# Sheet2.net
KiCad netlist of a schematic drawn in Altium Designer
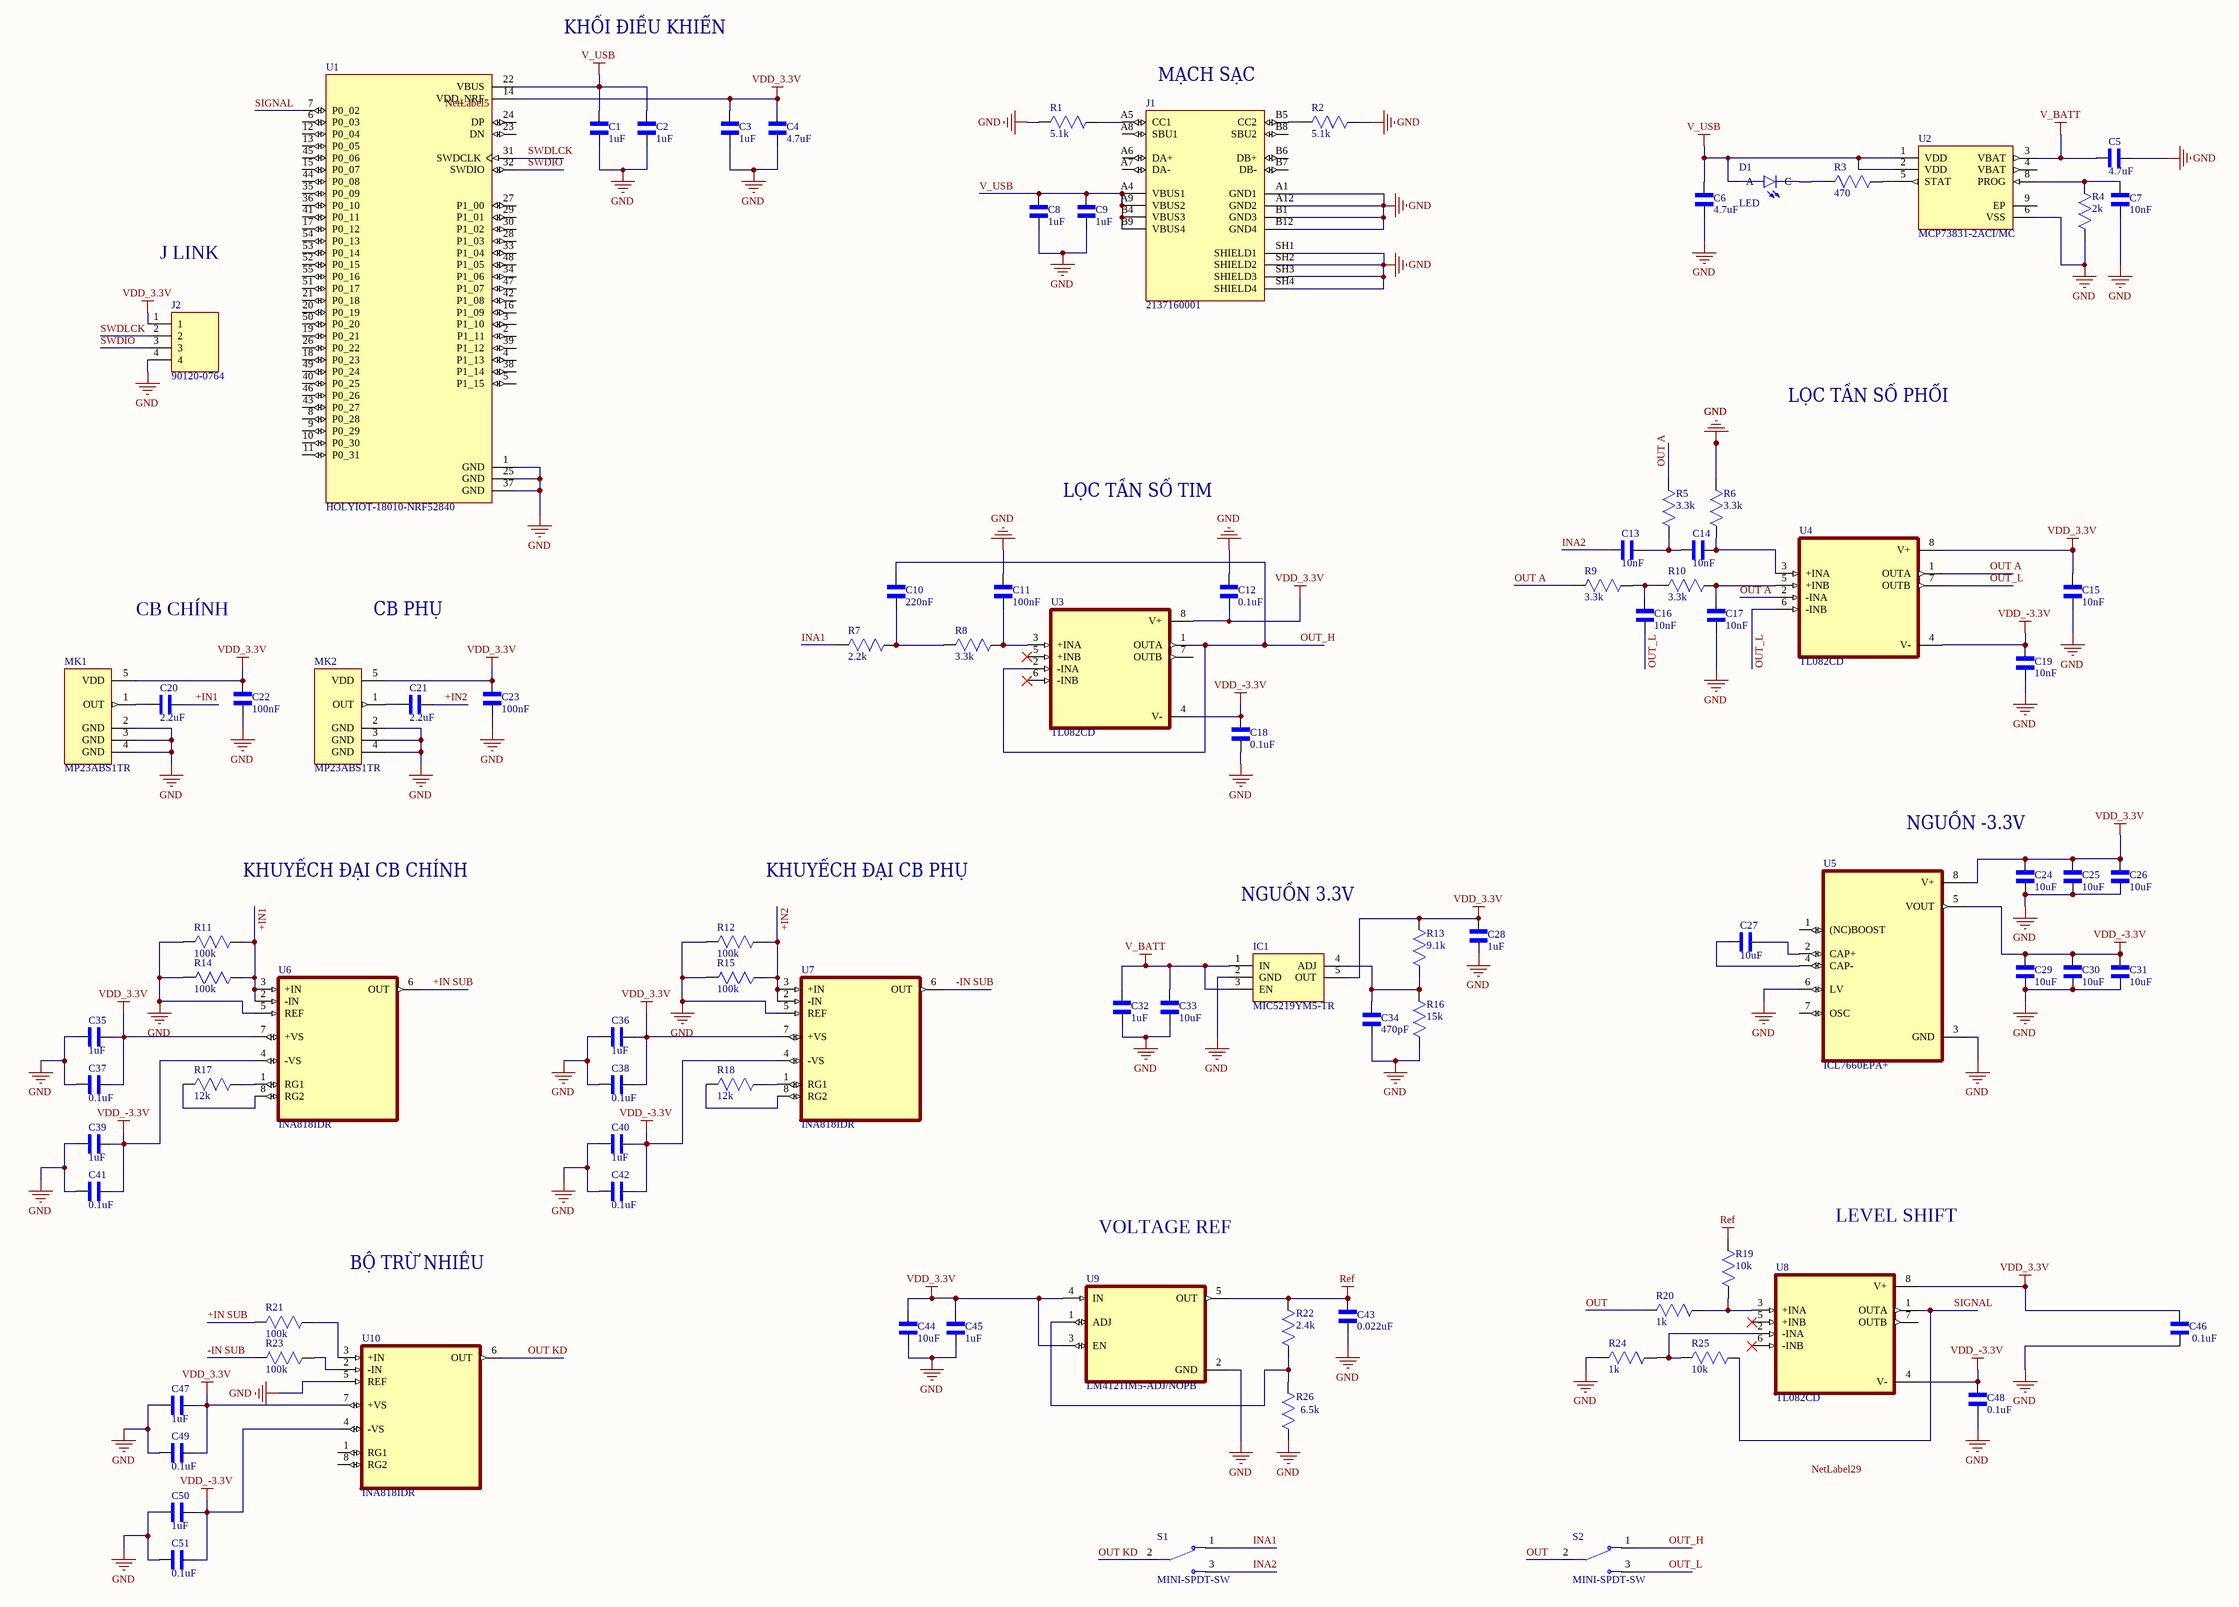
[diagram p0: Sheet2.SchDoc]

(export (version "E")
  (design (tool "Eeschema 10.0.6"))
  (components
    (comp (ref "C1")
      (value "1uF")
      (footprint "CAPC1608X90N")
      (description "0.1 ÂµF Â±10% 50V Ceramic Capacitor X7R 0603 (1608 Metric)")
      (fields (field (name "MF") "Samsung Electro-Mechanics") (field (name "MP") "CL10B104KB8NNNC"))
      (libsource (lib "") (part "CL10B104KB8NNNC_1"))
    )
    (comp (ref "C2")
      (value "1uF")
      (footprint "CAPC1608X90N")
      (description "0.1 ÂµF Â±10% 50V Ceramic Capacitor X7R 0603 (1608 Metric)")
      (fields (field (name "MF") "Samsung Electro-Mechanics") (field (name "MP") "CL10B104KB8NNNC"))
      (libsource (lib "") (part "CL10B104KB8NNNC_1"))
    )
    (comp (ref "C3")
      (value "1uF")
      (footprint "CAPC1608X90N")
      (description "0.1 ÂµF Â±10% 50V Ceramic Capacitor X7R 0603 (1608 Metric)")
      (fields (field (name "MF") "Samsung Electro-Mechanics") (field (name "MP") "CL10B104KB8NNNC"))
      (libsource (lib "") (part "CL10B104KB8NNNC_1"))
    )
    (comp (ref "C4")
      (value "4.7uF")
      (footprint "CAPC1608X90N")
      (description "0.1 ÂµF Â±10% 50V Ceramic Capacitor X7R 0603 (1608 Metric)")
      (fields (field (name "MF") "Samsung Electro-Mechanics") (field (name "MP") "CL10B104KB8NNNC"))
      (libsource (lib "") (part "CL10B104KB8NNNC_1"))
    )
    (comp (ref "C5")
      (value "4.7uF")
      (footprint "CAPC1608X90N")
      (description "0.1 ÂµF Â±10% 50V Ceramic Capacitor X7R 0603 (1608 Metric)")
      (fields (field (name "MF") "Samsung Electro-Mechanics") (field (name "MP") "CL10B104KB8NNNC"))
      (libsource (lib "") (part "CL10B104KB8NNNC_3"))
    )
    (comp (ref "C6")
      (value "4.7uF")
      (footprint "CAPC1608X90N")
      (description "0.1 ÂµF Â±10% 50V Ceramic Capacitor X7R 0603 (1608 Metric)")
      (fields (field (name "MF") "Samsung Electro-Mechanics") (field (name "MP") "CL10B104KB8NNNC"))
      (libsource (lib "") (part "CL10B104KB8NNNC_1"))
    )
    (comp (ref "C7")
      (value "10nF")
      (footprint "CAPC1608X90N")
      (description "0.1 ÂµF Â±10% 50V Ceramic Capacitor X7R 0603 (1608 Metric)")
      (fields (field (name "MF") "Samsung Electro-Mechanics") (field (name "MP") "CL10B104KB8NNNC"))
      (libsource (lib "") (part "CL10B104KB8NNNC_1"))
    )
    (comp (ref "C8")
      (value "1uF")
      (footprint "CAPC1608X90N")
      (description "0.1 ÂµF Â±10% 50V Ceramic Capacitor X7R 0603 (1608 Metric)")
      (fields (field (name "MF") "Samsung Electro-Mechanics") (field (name "MP") "CL10B104KB8NNNC"))
      (libsource (lib "") (part "CL10B104KB8NNNC_1"))
    )
    (comp (ref "C9")
      (value "1uF")
      (footprint "CAPC1608X90N")
      (description "0.1 ÂµF Â±10% 50V Ceramic Capacitor X7R 0603 (1608 Metric)")
      (fields (field (name "MF") "Samsung Electro-Mechanics") (field (name "MP") "CL10B104KB8NNNC"))
      (libsource (lib "") (part "CL10B104KB8NNNC_1"))
    )
    (comp (ref "C10")
      (value "220nF")
      (footprint "CAPC1608X90N")
      (description "0.1 ÂµF Â±10% 50V Ceramic Capacitor X7R 0603 (1608 Metric)")
      (fields (field (name "MF") "Samsung Electro-Mechanics") (field (name "MP") "CL10B104KB8NNNC"))
      (libsource (lib "Cap0603") (part "CL10B104KB8NNNC"))
    )
    (comp (ref "C11")
      (value "100nF")
      (footprint "CAPC1608X90N")
      (description "0.1 ÂµF Â±10% 50V Ceramic Capacitor X7R 0603 (1608 Metric)")
      (fields (field (name "MF") "Samsung Electro-Mechanics") (field (name "MP") "CL10B104KB8NNNC"))
      (libsource (lib "Cap0603") (part "CL10B104KB8NNNC"))
    )
    (comp (ref "C12")
      (value "0.1uF")
      (footprint "CAPC1608X90N")
      (description "0.1 ÂµF Â±10% 50V Ceramic Capacitor X7R 0603 (1608 Metric)")
      (fields (field (name "MF") "Samsung Electro-Mechanics") (field (name "MP") "CL10B104KB8NNNC"))
      (libsource (lib "Cap0603") (part "CL10B104KB8NNNC"))
    )
    (comp (ref "C13")
      (value "10nF")
      (footprint "CAPC1608X90N")
      (description "0.1 ÂµF Â±10% 50V Ceramic Capacitor X7R 0603 (1608 Metric)")
      (fields (field (name "MF") "Samsung Electro-Mechanics") (field (name "MP") "CL10B104KB8NNNC"))
      (libsource (lib "") (part "CL10B104KB8NNNC_2"))
    )
    (comp (ref "C14")
      (value "10nF")
      (footprint "CAPC1608X90N")
      (description "0.1 ÂµF Â±10% 50V Ceramic Capacitor X7R 0603 (1608 Metric)")
      (fields (field (name "MF") "Samsung Electro-Mechanics") (field (name "MP") "CL10B104KB8NNNC"))
      (libsource (lib "") (part "CL10B104KB8NNNC_2"))
    )
    (comp (ref "C15")
      (value "10nF")
      (footprint "CAPC1608X90N")
      (description "0.1 ÂµF Â±10% 50V Ceramic Capacitor X7R 0603 (1608 Metric)")
      (fields (field (name "MF") "Samsung Electro-Mechanics") (field (name "MP") "CL10B104KB8NNNC"))
      (libsource (lib "") (part "CL10B104KB8NNNC_1"))
    )
    (comp (ref "C16")
      (value "10nF")
      (footprint "CAPC1608X90N")
      (description "0.1 ÂµF Â±10% 50V Ceramic Capacitor X7R 0603 (1608 Metric)")
      (fields (field (name "MF") "Samsung Electro-Mechanics") (field (name "MP") "CL10B104KB8NNNC"))
      (libsource (lib "Cap0603") (part "CL10B104KB8NNNC"))
    )
    (comp (ref "C17")
      (value "10nF")
      (footprint "CAPC1608X90N")
      (description "0.1 ÂµF Â±10% 50V Ceramic Capacitor X7R 0603 (1608 Metric)")
      (fields (field (name "MF") "Samsung Electro-Mechanics") (field (name "MP") "CL10B104KB8NNNC"))
      (libsource (lib "Cap0603") (part "CL10B104KB8NNNC"))
    )
    (comp (ref "C18")
      (value "0.1uF")
      (footprint "CAPC1608X90N")
      (description "0.1 ÂµF Â±10% 50V Ceramic Capacitor X7R 0603 (1608 Metric)")
      (fields (field (name "MF") "Samsung Electro-Mechanics") (field (name "MP") "CL10B104KB8NNNC"))
      (libsource (lib "Cap0603") (part "CL10B104KB8NNNC"))
    )
    (comp (ref "C19")
      (value "10nF")
      (footprint "CAPC1608X90N")
      (description "0.1 ÂµF Â±10% 50V Ceramic Capacitor X7R 0603 (1608 Metric)")
      (fields (field (name "MF") "Samsung Electro-Mechanics") (field (name "MP") "CL10B104KB8NNNC"))
      (libsource (lib "") (part "CL10B104KB8NNNC_1"))
    )
    (comp (ref "C20")
      (value "2.2uF")
      (footprint "CAPC1608X90N")
      (description "0.1 ÂµF Â±10% 50V Ceramic Capacitor X7R 0603 (1608 Metric)")
      (fields (field (name "MF") "Samsung Electro-Mechanics") (field (name "MP") "CL10B104KB8NNNC"))
      (libsource (lib "") (part "CL10B104KB8NNNC_2"))
    )
    (comp (ref "C21")
      (value "2.2uF")
      (footprint "CAPC1608X90N")
      (description "0.1 ÂµF Â±10% 50V Ceramic Capacitor X7R 0603 (1608 Metric)")
      (fields (field (name "MF") "Samsung Electro-Mechanics") (field (name "MP") "CL10B104KB8NNNC"))
      (libsource (lib "") (part "CL10B104KB8NNNC_2"))
    )
    (comp (ref "C22")
      (value "100nF")
      (footprint "CAPC1608X90N")
      (description "0.1 ÂµF Â±10% 50V Ceramic Capacitor X7R 0603 (1608 Metric)")
      (fields (field (name "MF") "Samsung Electro-Mechanics") (field (name "MP") "CL10B104KB8NNNC"))
      (libsource (lib "") (part "CL10B104KB8NNNC_1"))
    )
    (comp (ref "C23")
      (value "100nF")
      (footprint "CAPC1608X90N")
      (description "0.1 ÂµF Â±10% 50V Ceramic Capacitor X7R 0603 (1608 Metric)")
      (fields (field (name "MF") "Samsung Electro-Mechanics") (field (name "MP") "CL10B104KB8NNNC"))
      (libsource (lib "") (part "CL10B104KB8NNNC_1"))
    )
    (comp (ref "C24")
      (value "10uF")
      (footprint "CAPC1608X90N")
      (description "0.1 ÂµF Â±10% 50V Ceramic Capacitor X7R 0603 (1608 Metric)")
      (fields (field (name "MF") "Samsung Electro-Mechanics") (field (name "MP") "CL10B104KB8NNNC"))
      (libsource (lib "") (part "CL10B104KB8NNNC_1"))
    )
    (comp (ref "C25")
      (value "10uF")
      (footprint "CAPC1608X90N")
      (description "0.1 ÂµF Â±10% 50V Ceramic Capacitor X7R 0603 (1608 Metric)")
      (fields (field (name "MF") "Samsung Electro-Mechanics") (field (name "MP") "CL10B104KB8NNNC"))
      (libsource (lib "") (part "CL10B104KB8NNNC_1"))
    )
    (comp (ref "C26")
      (value "10uF")
      (footprint "CAPC1608X90N")
      (description "0.1 ÂµF Â±10% 50V Ceramic Capacitor X7R 0603 (1608 Metric)")
      (fields (field (name "MF") "Samsung Electro-Mechanics") (field (name "MP") "CL10B104KB8NNNC"))
      (libsource (lib "") (part "CL10B104KB8NNNC_1"))
    )
    (comp (ref "C27")
      (value "10uF")
      (footprint "CAPC1608X90N")
      (description "0.1 ÂµF Â±10% 50V Ceramic Capacitor X7R 0603 (1608 Metric)")
      (fields (field (name "MF") "Samsung Electro-Mechanics") (field (name "MP") "CL10B104KB8NNNC"))
      (libsource (lib "") (part "CL10B104KB8NNNC_3"))
    )
    (comp (ref "C28")
      (value "1uF")
      (footprint "CAPC1608X90N")
      (description "0.1 ÂµF Â±10% 50V Ceramic Capacitor X7R 0603 (1608 Metric)")
      (fields (field (name "MF") "Samsung Electro-Mechanics") (field (name "MP") "CL10B104KB8NNNC"))
      (libsource (lib "Cap0603") (part "CL10B104KB8NNNC"))
    )
    (comp (ref "C29")
      (value "10uF")
      (footprint "CAPC1608X90N")
      (description "0.1 ÂµF Â±10% 50V Ceramic Capacitor X7R 0603 (1608 Metric)")
      (fields (field (name "MF") "Samsung Electro-Mechanics") (field (name "MP") "CL10B104KB8NNNC"))
      (libsource (lib "") (part "CL10B104KB8NNNC_1"))
    )
    (comp (ref "C30")
      (value "10uF")
      (footprint "CAPC1608X90N")
      (description "0.1 ÂµF Â±10% 50V Ceramic Capacitor X7R 0603 (1608 Metric)")
      (fields (field (name "MF") "Samsung Electro-Mechanics") (field (name "MP") "CL10B104KB8NNNC"))
      (libsource (lib "") (part "CL10B104KB8NNNC_1"))
    )
    (comp (ref "C31")
      (value "10uF")
      (footprint "CAPC1608X90N")
      (description "0.1 ÂµF Â±10% 50V Ceramic Capacitor X7R 0603 (1608 Metric)")
      (fields (field (name "MF") "Samsung Electro-Mechanics") (field (name "MP") "CL10B104KB8NNNC"))
      (libsource (lib "") (part "CL10B104KB8NNNC_1"))
    )
    (comp (ref "C32")
      (value "1uF")
      (footprint "CAPC1608X90N")
      (description "0.1 ÂµF Â±10% 50V Ceramic Capacitor X7R 0603 (1608 Metric)")
      (fields (field (name "MF") "Samsung Electro-Mechanics") (field (name "MP") "CL10B104KB8NNNC"))
      (libsource (lib "Cap0603") (part "CL10B104KB8NNNC"))
    )
    (comp (ref "C33")
      (value "10uF")
      (footprint "CAPC1608X90N")
      (description "0.1 ÂµF Â±10% 50V Ceramic Capacitor X7R 0603 (1608 Metric)")
      (fields (field (name "MF") "Samsung Electro-Mechanics") (field (name "MP") "CL10B104KB8NNNC"))
      (libsource (lib "Cap0603") (part "CL10B104KB8NNNC"))
    )
    (comp (ref "C34")
      (value "470pF")
      (footprint "CAPC1608X90N")
      (description "0.1 ÂµF Â±10% 50V Ceramic Capacitor X7R 0603 (1608 Metric)")
      (fields (field (name "MF") "Samsung Electro-Mechanics") (field (name "MP") "CL10B104KB8NNNC"))
      (libsource (lib "Cap0603") (part "CL10B104KB8NNNC"))
    )
    (comp (ref "C35")
      (value "1uF")
      (footprint "CAPC1608X90N")
      (description "0.1 ÂµF Â±10% 50V Ceramic Capacitor X7R 0603 (1608 Metric)")
      (fields (field (name "MF") "Samsung Electro-Mechanics") (field (name "MP") "CL10B104KB8NNNC"))
      (libsource (lib "") (part "CL10B104KB8NNNC_2"))
    )
    (comp (ref "C36")
      (value "1uF")
      (footprint "CAPC1608X90N")
      (description "0.1 ÂµF Â±10% 50V Ceramic Capacitor X7R 0603 (1608 Metric)")
      (fields (field (name "MF") "Samsung Electro-Mechanics") (field (name "MP") "CL10B104KB8NNNC"))
      (libsource (lib "") (part "CL10B104KB8NNNC_2"))
    )
    (comp (ref "C37")
      (value "0.1uF")
      (footprint "CAPC1608X90N")
      (description "0.1 ÂµF Â±10% 50V Ceramic Capacitor X7R 0603 (1608 Metric)")
      (fields (field (name "MF") "Samsung Electro-Mechanics") (field (name "MP") "CL10B104KB8NNNC"))
      (libsource (lib "") (part "CL10B104KB8NNNC_2"))
    )
    (comp (ref "C38")
      (value "0.1uF")
      (footprint "CAPC1608X90N")
      (description "0.1 ÂµF Â±10% 50V Ceramic Capacitor X7R 0603 (1608 Metric)")
      (fields (field (name "MF") "Samsung Electro-Mechanics") (field (name "MP") "CL10B104KB8NNNC"))
      (libsource (lib "") (part "CL10B104KB8NNNC_2"))
    )
    (comp (ref "C39")
      (value "1uF")
      (footprint "CAPC1608X90N")
      (description "0.1 ÂµF Â±10% 50V Ceramic Capacitor X7R 0603 (1608 Metric)")
      (fields (field (name "MF") "Samsung Electro-Mechanics") (field (name "MP") "CL10B104KB8NNNC"))
      (libsource (lib "") (part "CL10B104KB8NNNC_2"))
    )
    (comp (ref "C40")
      (value "1uF")
      (footprint "CAPC1608X90N")
      (description "0.1 ÂµF Â±10% 50V Ceramic Capacitor X7R 0603 (1608 Metric)")
      (fields (field (name "MF") "Samsung Electro-Mechanics") (field (name "MP") "CL10B104KB8NNNC"))
      (libsource (lib "") (part "CL10B104KB8NNNC_2"))
    )
    (comp (ref "C41")
      (value "0.1uF")
      (footprint "CAPC1608X90N")
      (description "0.1 ÂµF Â±10% 50V Ceramic Capacitor X7R 0603 (1608 Metric)")
      (fields (field (name "MF") "Samsung Electro-Mechanics") (field (name "MP") "CL10B104KB8NNNC"))
      (libsource (lib "") (part "CL10B104KB8NNNC_2"))
    )
    (comp (ref "C42")
      (value "0.1uF")
      (footprint "CAPC1608X90N")
      (description "0.1 ÂµF Â±10% 50V Ceramic Capacitor X7R 0603 (1608 Metric)")
      (fields (field (name "MF") "Samsung Electro-Mechanics") (field (name "MP") "CL10B104KB8NNNC"))
      (libsource (lib "") (part "CL10B104KB8NNNC_2"))
    )
    (comp (ref "C43")
      (value "0.022uF")
      (footprint "CAPC1608X90N")
      (description "0.1 ÂµF Â±10% 50V Ceramic Capacitor X7R 0603 (1608 Metric)")
      (fields (field (name "MF") "Samsung Electro-Mechanics") (field (name "MP") "CL10B104KB8NNNC"))
      (libsource (lib "Cap0603") (part "CL10B104KB8NNNC"))
    )
    (comp (ref "C44")
      (value "10uF")
      (footprint "CAPC1608X90N")
      (description "0.1 ÂµF Â±10% 50V Ceramic Capacitor X7R 0603 (1608 Metric)")
      (fields (field (name "MF") "Samsung Electro-Mechanics") (field (name "MP") "CL10B104KB8NNNC"))
      (libsource (lib "Cap0603") (part "CL10B104KB8NNNC"))
    )
    (comp (ref "C45")
      (value "1uF")
      (footprint "CAPC1608X90N")
      (description "0.1 ÂµF Â±10% 50V Ceramic Capacitor X7R 0603 (1608 Metric)")
      (fields (field (name "MF") "Samsung Electro-Mechanics") (field (name "MP") "CL10B104KB8NNNC"))
      (libsource (lib "Cap0603") (part "CL10B104KB8NNNC"))
    )
    (comp (ref "C46")
      (value "0.1uF")
      (footprint "CAPC1608X90N")
      (description "0.1 ÂµF Â±10% 50V Ceramic Capacitor X7R 0603 (1608 Metric)")
      (fields (field (name "MF") "Samsung Electro-Mechanics") (field (name "MP") "CL10B104KB8NNNC"))
      (libsource (lib "") (part "CL10B104KB8NNNC_1"))
    )
    (comp (ref "C47")
      (value "1uF")
      (footprint "CAPC1608X90N")
      (description "0.1 ÂµF Â±10% 50V Ceramic Capacitor X7R 0603 (1608 Metric)")
      (fields (field (name "MF") "Samsung Electro-Mechanics") (field (name "MP") "CL10B104KB8NNNC"))
      (libsource (lib "") (part "CL10B104KB8NNNC_2"))
    )
    (comp (ref "C48")
      (value "0.1uF")
      (footprint "CAPC1608X90N")
      (description "0.1 ÂµF Â±10% 50V Ceramic Capacitor X7R 0603 (1608 Metric)")
      (fields (field (name "MF") "Samsung Electro-Mechanics") (field (name "MP") "CL10B104KB8NNNC"))
      (libsource (lib "") (part "CL10B104KB8NNNC_1"))
    )
    (comp (ref "C49")
      (value "0.1uF")
      (footprint "CAPC1608X90N")
      (description "0.1 ÂµF Â±10% 50V Ceramic Capacitor X7R 0603 (1608 Metric)")
      (fields (field (name "MF") "Samsung Electro-Mechanics") (field (name "MP") "CL10B104KB8NNNC"))
      (libsource (lib "") (part "CL10B104KB8NNNC_2"))
    )
    (comp (ref "C50")
      (value "1uF")
      (footprint "CAPC1608X90N")
      (description "0.1 ÂµF Â±10% 50V Ceramic Capacitor X7R 0603 (1608 Metric)")
      (fields (field (name "MF") "Samsung Electro-Mechanics") (field (name "MP") "CL10B104KB8NNNC"))
      (libsource (lib "") (part "CL10B104KB8NNNC_2"))
    )
    (comp (ref "C51")
      (value "0.1uF")
      (footprint "CAPC1608X90N")
      (description "0.1 ÂµF Â±10% 50V Ceramic Capacitor X7R 0603 (1608 Metric)")
      (fields (field (name "MF") "Samsung Electro-Mechanics") (field (name "MP") "CL10B104KB8NNNC"))
      (libsource (lib "") (part "CL10B104KB8NNNC_2"))
    )
    (comp (ref "D1")
      (value "LED")
      (footprint "LEDC2012X70N")
      (description "SMD LED 0805 YG 7 ¦ Dialight 597-5411-407F")
      (fields (field (name "MF") "Dialight") (field (name "MP") "597-5411-407F"))
      (libsource (lib "LED0805") (part "597-5411-407F"))
    )
    (comp (ref "IC1")
      (value "MIC5219YM5-TR")
      (footprint "SamacSys:SOT95P280X145-5N")
      (description "Integrated Circuit")
      (fields (field (name "MOUSER PART NUMBER") "998-MIC5219YM5TR"))
      (libsource (lib "*") (part "MIC5219YM5-TR"))
    )
    (comp (ref "J1")
      (value "2137160001")
      (footprint "MOLEX_2137160001")
      (description "USB-C (USB TYPE-C) USB 2.0 Receptacle Connector 24 (16+8 Dummy) Position Through Hole, Right Angle")
      (fields (field (name "MF") "Molex"))
      (libsource (lib "2137160001") (part "2137160001"))
    )
    (comp (ref "J2")
      (value "90120-0764")
      (footprint "SamacSys:HDRV4W90P0X254_1X4_994X249X560P")
      (description "Connector")
      (fields (field (name "MOUSER PART NUMBER") "538-90120-0764"))
      (libsource (lib "*") (part "90120-0764"))
    )
    (comp (ref "MK1")
      (value "MP23ABS1TR")
      (footprint "MIC_MP23ABS1TR")
      (fields (field (name "MF") "STMicroelectronics"))
      (libsource (lib "MP23ABS1TR") (part "MP23ABS1TR"))
    )
    (comp (ref "MK2")
      (value "MP23ABS1TR")
      (footprint "MIC_MP23ABS1TR")
      (fields (field (name "MF") "STMicroelectronics"))
      (libsource (lib "MP23ABS1TR") (part "MP23ABS1TR"))
    )
    (comp (ref "R1")
      (value "5.1k")
      (footprint "RESC1608X60N")
      (description "51 Ohms Â±1% 0.1W, 1/10W Chip Resistor 0603 (1608 Metric) Moisture Resistant Thick Film")
      (fields (field (name "MF") "Yageo Corporation") (field (name "MP") "RC0603FR0751RL"))
      (libsource (lib "RC0603") (part "RC0603FR-0751RL"))
    )
    (comp (ref "R2")
      (value "5.1k")
      (footprint "RESC1608X60N")
      (description "51 Ohms Â±1% 0.1W, 1/10W Chip Resistor 0603 (1608 Metric) Moisture Resistant Thick Film")
      (fields (field (name "MF") "Yageo Corporation") (field (name "MP") "RC0603FR0751RL"))
      (libsource (lib "RC0603") (part "RC0603FR-0751RL"))
    )
    (comp (ref "R3")
      (value "470")
      (footprint "RESC1608X60N")
      (description "51 Ohms Â±1% 0.1W, 1/10W Chip Resistor 0603 (1608 Metric) Moisture Resistant Thick Film")
      (fields (field (name "MF") "Yageo Corporation") (field (name "MP") "RC0603FR0751RL"))
      (libsource (lib "RC0603") (part "RC0603FR-0751RL"))
    )
    (comp (ref "R4")
      (value "2k")
      (footprint "RESC1608X60N")
      (description "51 Ohms Â±1% 0.1W, 1/10W Chip Resistor 0603 (1608 Metric) Moisture Resistant Thick Film")
      (fields (field (name "MF") "Yageo Corporation") (field (name "MP") "RC0603FR0751RL"))
      (libsource (lib "RC0603") (part "RC0603FR-0751RL"))
    )
    (comp (ref "R5")
      (value "3.3k")
      (footprint "RESC1608X60N")
      (description "51 Ohms Â±1% 0.1W, 1/10W Chip Resistor 0603 (1608 Metric) Moisture Resistant Thick Film")
      (fields (field (name "MF") "Yageo Corporation") (field (name "MP") "RC0603FR0751RL"))
      (libsource (lib "RC0603") (part "RC0603FR-0751RL"))
    )
    (comp (ref "R6")
      (value "3.3k")
      (footprint "RESC1608X60N")
      (description "51 Ohms Â±1% 0.1W, 1/10W Chip Resistor 0603 (1608 Metric) Moisture Resistant Thick Film")
      (fields (field (name "MF") "Yageo Corporation") (field (name "MP") "RC0603FR0751RL"))
      (libsource (lib "RC0603") (part "RC0603FR-0751RL"))
    )
    (comp (ref "R7")
      (value "2.2k")
      (footprint "RESC1608X60N")
      (description "51 Ohms Â±1% 0.1W, 1/10W Chip Resistor 0603 (1608 Metric) Moisture Resistant Thick Film")
      (fields (field (name "MF") "Yageo Corporation") (field (name "MP") "RC0603FR0751RL"))
      (libsource (lib "RC0603") (part "RC0603FR-0751RL"))
    )
    (comp (ref "R8")
      (value "3.3k")
      (footprint "RESC1608X60N")
      (description "51 Ohms Â±1% 0.1W, 1/10W Chip Resistor 0603 (1608 Metric) Moisture Resistant Thick Film")
      (fields (field (name "MF") "Yageo Corporation") (field (name "MP") "RC0603FR0751RL"))
      (libsource (lib "RC0603") (part "RC0603FR-0751RL"))
    )
    (comp (ref "R9")
      (value "3.3k")
      (footprint "RESC1608X60N")
      (description "51 Ohms Â±1% 0.1W, 1/10W Chip Resistor 0603 (1608 Metric) Moisture Resistant Thick Film")
      (fields (field (name "MF") "Yageo Corporation") (field (name "MP") "RC0603FR0751RL"))
      (libsource (lib "RC0603") (part "RC0603FR-0751RL"))
    )
    (comp (ref "R10")
      (value "3.3k")
      (footprint "RESC1608X60N")
      (description "51 Ohms Â±1% 0.1W, 1/10W Chip Resistor 0603 (1608 Metric) Moisture Resistant Thick Film")
      (fields (field (name "MF") "Yageo Corporation") (field (name "MP") "RC0603FR0751RL"))
      (libsource (lib "RC0603") (part "RC0603FR-0751RL"))
    )
    (comp (ref "R11")
      (value "100k")
      (footprint "RESC1608X60N")
      (description "51 Ohms Â±1% 0.1W, 1/10W Chip Resistor 0603 (1608 Metric) Moisture Resistant Thick Film")
      (fields (field (name "MF") "Yageo Corporation") (field (name "MP") "RC0603FR0751RL"))
      (libsource (lib "RC0603") (part "RC0603FR-0751RL"))
    )
    (comp (ref "R12")
      (value "100k")
      (footprint "RESC1608X60N")
      (description "51 Ohms Â±1% 0.1W, 1/10W Chip Resistor 0603 (1608 Metric) Moisture Resistant Thick Film")
      (fields (field (name "MF") "Yageo Corporation") (field (name "MP") "RC0603FR0751RL"))
      (libsource (lib "RC0603") (part "RC0603FR-0751RL"))
    )
    (comp (ref "R13")
      (value "9.1k")
      (footprint "RESC1608X60N")
      (description "51 Ohms Â±1% 0.1W, 1/10W Chip Resistor 0603 (1608 Metric) Moisture Resistant Thick Film")
      (fields (field (name "MF") "Yageo Corporation") (field (name "MP") "RC0603FR0751RL"))
      (libsource (lib "RC0603") (part "RC0603FR-0751RL"))
    )
    (comp (ref "R14")
      (value "100k")
      (footprint "RESC1608X60N")
      (description "51 Ohms Â±1% 0.1W, 1/10W Chip Resistor 0603 (1608 Metric) Moisture Resistant Thick Film")
      (fields (field (name "MF") "Yageo Corporation") (field (name "MP") "RC0603FR0751RL"))
      (libsource (lib "RC0603") (part "RC0603FR-0751RL"))
    )
    (comp (ref "R15")
      (value "100k")
      (footprint "RESC1608X60N")
      (description "51 Ohms Â±1% 0.1W, 1/10W Chip Resistor 0603 (1608 Metric) Moisture Resistant Thick Film")
      (fields (field (name "MF") "Yageo Corporation") (field (name "MP") "RC0603FR0751RL"))
      (libsource (lib "RC0603") (part "RC0603FR-0751RL"))
    )
    (comp (ref "R16")
      (value "15k")
      (footprint "RESC1608X60N")
      (description "51 Ohms Â±1% 0.1W, 1/10W Chip Resistor 0603 (1608 Metric) Moisture Resistant Thick Film")
      (fields (field (name "MF") "Yageo Corporation") (field (name "MP") "RC0603FR0751RL"))
      (libsource (lib "RC0603") (part "RC0603FR-0751RL"))
    )
    (comp (ref "R17")
      (value "12k")
      (footprint "RESC1608X60N")
      (description "51 Ohms Â±1% 0.1W, 1/10W Chip Resistor 0603 (1608 Metric) Moisture Resistant Thick Film")
      (fields (field (name "MF") "Yageo Corporation") (field (name "MP") "RC0603FR0751RL"))
      (libsource (lib "RC0603") (part "RC0603FR-0751RL"))
    )
    (comp (ref "R18")
      (value "12k")
      (footprint "RESC1608X60N")
      (description "51 Ohms Â±1% 0.1W, 1/10W Chip Resistor 0603 (1608 Metric) Moisture Resistant Thick Film")
      (fields (field (name "MF") "Yageo Corporation") (field (name "MP") "RC0603FR0751RL"))
      (libsource (lib "RC0603") (part "RC0603FR-0751RL"))
    )
    (comp (ref "R19")
      (value "10k")
      (footprint "RESC1608X60N")
      (description "51 Ohms Â±1% 0.1W, 1/10W Chip Resistor 0603 (1608 Metric) Moisture Resistant Thick Film")
      (fields (field (name "MF") "Yageo Corporation") (field (name "MP") "RC0603FR0751RL"))
      (libsource (lib "RC0603") (part "RC0603FR-0751RL"))
    )
    (comp (ref "R20")
      (value "1k")
      (footprint "RESC1608X60N")
      (description "51 Ohms Â±1% 0.1W, 1/10W Chip Resistor 0603 (1608 Metric) Moisture Resistant Thick Film")
      (fields (field (name "MF") "Yageo Corporation") (field (name "MP") "RC0603FR0751RL"))
      (libsource (lib "RC0603") (part "RC0603FR-0751RL"))
    )
    (comp (ref "R21")
      (value "100k")
      (footprint "RESC1608X60N")
      (description "51 Ohms Â±1% 0.1W, 1/10W Chip Resistor 0603 (1608 Metric) Moisture Resistant Thick Film")
      (fields (field (name "MF") "Yageo Corporation") (field (name "MP") "RC0603FR0751RL"))
      (libsource (lib "RC0603") (part "RC0603FR-0751RL"))
    )
    (comp (ref "R22")
      (value "2.4k")
      (footprint "RESC1608X60N")
      (description "51 Ohms Â±1% 0.1W, 1/10W Chip Resistor 0603 (1608 Metric) Moisture Resistant Thick Film")
      (fields (field (name "MF") "Yageo Corporation") (field (name "MP") "RC0603FR0751RL"))
      (libsource (lib "RC0603") (part "RC0603FR-0751RL"))
    )
    (comp (ref "R23")
      (value "100k")
      (footprint "RESC1608X60N")
      (description "51 Ohms Â±1% 0.1W, 1/10W Chip Resistor 0603 (1608 Metric) Moisture Resistant Thick Film")
      (fields (field (name "MF") "Yageo Corporation") (field (name "MP") "RC0603FR0751RL"))
      (libsource (lib "RC0603") (part "RC0603FR-0751RL"))
    )
    (comp (ref "R24")
      (value "1k")
      (footprint "RESC1608X60N")
      (description "51 Ohms Â±1% 0.1W, 1/10W Chip Resistor 0603 (1608 Metric) Moisture Resistant Thick Film")
      (fields (field (name "MF") "Yageo Corporation") (field (name "MP") "RC0603FR0751RL"))
      (libsource (lib "RC0603") (part "RC0603FR-0751RL"))
    )
    (comp (ref "R25")
      (value "10k")
      (footprint "RESC1608X60N")
      (description "51 Ohms Â±1% 0.1W, 1/10W Chip Resistor 0603 (1608 Metric) Moisture Resistant Thick Film")
      (fields (field (name "MF") "Yageo Corporation") (field (name "MP") "RC0603FR0751RL"))
      (libsource (lib "RC0603") (part "RC0603FR-0751RL"))
    )
    (comp (ref "R26")
      (value "6.5k")
      (footprint "RESC1608X60N")
      (description "51 Ohms Â±1% 0.1W, 1/10W Chip Resistor 0603 (1608 Metric) Moisture Resistant Thick Film")
      (fields (field (name "MF") "Yageo Corporation") (field (name "MP") "RC0603FR0751RL"))
      (libsource (lib "RC0603") (part "RC0603FR-0751RL"))
    )
    (comp (ref "S1")
      (value "MINI-SPDT-SW")
      (footprint "SW_MINI-SPDT-SW")
      (libsource (lib "MINI-SPDT-SW") (part "MINI-SPDT-SW"))
    )
    (comp (ref "S2")
      (value "MINI-SPDT-SW")
      (footprint "SW_MINI-SPDT-SW")
      (libsource (lib "MINI-SPDT-SW") (part "MINI-SPDT-SW"))
    )
    (comp (ref "U1")
      (value "HOLYIOT-18010-NRF52840")
      (footprint "XCVR_HOLYIOT-18010-NRF52840")
      (description "Holyiot 18010 Nordic nRF52840 module Bluetooth low energy module")
      (fields (field (name "MF") "Holyiot"))
      (libsource (lib "HOLYIOT-18010-NRF52840") (part "HOLYIOT-18010-NRF52840"))
    )
    (comp (ref "U2")
      (value "MCP73831-2ACI/MC")
      (footprint "SON50P200X300X100-9N")
      (fields (field (name "MF") "Microchip"))
      (libsource (lib "MCP73831-2ACI_MC") (part "MCP73831-2ACI/MC"))
    )
    (comp (ref "U3")
      (value "TL082CD")
      (footprint "SOIC127P599X175-8N")
      (description "Dual, 30-V, 3-MHz, 13-V/Âµs slew rate, In to V+, JFET-input op amp")
      (fields (field (name "MF") "Texas Instruments"))
      (libsource (lib "TL082CD") (part "TL082CD"))
    )
    (comp (ref "U4")
      (value "TL082CD")
      (footprint "SOIC127P599X175-8N")
      (description "Dual, 30-V, 3-MHz, 13-V/Âµs slew rate, In to V+, JFET-input op amp")
      (fields (field (name "MF") "Texas Instruments"))
      (libsource (lib "TL082CD") (part "TL082CD"))
    )
    (comp (ref "U5")
      (value "ICL7660EPA+")
      (footprint "DIP794W47P254L991H457Q8")
      (description "Switched-Capacitor Voltage Converters")
      (fields (field (name "MF") "Analog Devices"))
      (libsource (lib "ICL7660EPA_") (part "ICL7660EPA+"))
    )
    (comp (ref "U6")
      (value "INA818IDR")
      (footprint "SOIC127P599X175-8N")
      (fields (field (name "MF") "Texas Instruments"))
      (libsource (lib "INA818IDR") (part "INA818IDR"))
    )
    (comp (ref "U7")
      (value "INA818IDR")
      (footprint "SOIC127P599X175-8N")
      (fields (field (name "MF") "Texas Instruments"))
      (libsource (lib "INA818IDR") (part "INA818IDR"))
    )
    (comp (ref "U8")
      (value "TL082CD")
      (footprint "SOIC127P599X175-8N")
      (description "Dual, 30-V, 3-MHz, 13-V/Âµs slew rate, In to V+, JFET-input op amp")
      (fields (field (name "MF") "Texas Instruments"))
      (libsource (lib "TL082CD") (part "TL082CD"))
    )
    (comp (ref "U9")
      (value "LM4121IM5-ADJ/NOPB")
      (footprint "SOT95P280X145-5N")
      (fields (field (name "MF") "Texas Instruments"))
      (libsource (lib "LM4121IM5-ADJ_NOPB") (part "LM4121IM5-ADJ/NOPB"))
    )
    (comp (ref "U10")
      (value "INA818IDR")
      (footprint "SOIC127P599X175-8N")
      (fields (field (name "MF") "Texas Instruments"))
      (libsource (lib "INA818IDR") (part "INA818IDR"))
    )
  )
  (nets
    (net (code "1") (name "/+IN SUB") (class "Default")
      (node (ref "R21") (pin "2") (pinfunction "R2_2") (pintype "passive"))
      (node (ref "U6") (pin "6") (pinfunction "OUT_6") (pintype "output"))
    )
    (net (code "2") (name "/+IN1") (class "Default")
      (node (ref "C20") (pin "1") (pinfunction "1_1") (pintype "passive"))
      (node (ref "R11") (pin "1") (pinfunction "R1_1") (pintype "passive"))
      (node (ref "R14") (pin "2") (pinfunction "R2_2") (pintype "passive"))
      (node (ref "U6") (pin "2") (pinfunction "-IN_2") (pintype "input"))
      (node (ref "U6") (pin "3") (pinfunction "+IN_3") (pintype "input"))
    )
    (net (code "3") (name "/+IN2") (class "Default")
      (node (ref "C21") (pin "1") (pinfunction "1_1") (pintype "passive"))
      (node (ref "R12") (pin "1") (pinfunction "R1_1") (pintype "passive"))
      (node (ref "R15") (pin "2") (pinfunction "R2_2") (pintype "passive"))
      (node (ref "U7") (pin "2") (pinfunction "-IN_2") (pintype "input"))
      (node (ref "U7") (pin "3") (pinfunction "+IN_3") (pintype "input"))
    )
    (net (code "4") (name "/-IN SUB") (class "Default")
      (node (ref "R23") (pin "1") (pinfunction "R1_1") (pintype "passive"))
      (node (ref "U7") (pin "6") (pinfunction "OUT_6") (pintype "output"))
    )
    (net (code "5") (name "/INA1") (class "Default")
      (node (ref "R7") (pin "2") (pinfunction "R2_2") (pintype "passive"))
      (node (ref "S1") (pin "1") (pinfunction "1_1") (pintype "passive"))
    )
    (net (code "6") (name "/INA2") (class "Default")
      (node (ref "C13") (pin "2") (pinfunction "2_2") (pintype "passive"))
      (node (ref "S1") (pin "3") (pinfunction "3_3") (pintype "passive"))
    )
    (net (code "9") (name "/OUT") (class "Default")
      (node (ref "R20") (pin "2") (pinfunction "R2_2") (pintype "passive"))
      (node (ref "S2") (pin "2") (pinfunction "2_2") (pintype "passive"))
    )
    (net (code "10") (name "/OUT A") (class "Default")
      (node (ref "R5") (pin "1") (pinfunction "R1_1") (pintype "passive"))
      (node (ref "R9") (pin "2") (pinfunction "R2_2") (pintype "passive"))
      (node (ref "U4") (pin "1") (pinfunction "OUTA_1") (pintype "output"))
      (node (ref "U4") (pin "2") (pinfunction "-INA_2") (pintype "input"))
    )
    (net (code "11") (name "/OUT KD") (class "Default")
      (node (ref "S1") (pin "2") (pinfunction "2_2") (pintype "passive"))
      (node (ref "U10") (pin "6") (pinfunction "OUT_6") (pintype "output"))
    )
    (net (code "12") (name "/OUT_H") (class "Default")
      (node (ref "C10") (pin "1") (pinfunction "1_1") (pintype "passive"))
      (node (ref "S2") (pin "1") (pinfunction "1_1") (pintype "passive"))
      (node (ref "U3") (pin "1") (pinfunction "OUTA_1") (pintype "output"))
      (node (ref "U3") (pin "2") (pinfunction "-INA_2") (pintype "input"))
    )
    (net (code "13") (name "/OUT_L") (class "Default")
      (node (ref "C16") (pin "2") (pinfunction "2_2") (pintype "passive"))
      (node (ref "S2") (pin "3") (pinfunction "3_3") (pintype "passive"))
      (node (ref "U4") (pin "6") (pinfunction "-INB_6") (pintype "input"))
      (node (ref "U4") (pin "7") (pinfunction "OUTB_7") (pintype "output"))
    )
    (net (code "14") (name "/SIGNAL") (class "Default")
      (node (ref "R25") (pin "1") (pinfunction "R1_1") (pintype "passive"))
      (node (ref "U1") (pin "7") (pinfunction "P0_02_7") (pintype "bidirectional"))
      (node (ref "U8") (pin "1") (pinfunction "OUTA_1") (pintype "output"))
    )
    (net (code "15") (name "/SWDIO") (class "Default")
      (node (ref "J2") (pin "3") (pinfunction "3_3") (pintype "passive"))
      (node (ref "U1") (pin "32") (pinfunction "SWDIO_32") (pintype "bidirectional"))
    )
    (net (code "16") (name "/SWDLCK") (class "Default")
      (node (ref "J2") (pin "2") (pinfunction "2_2") (pintype "passive"))
      (node (ref "U1") (pin "31") (pinfunction "SWDCLK_31") (pintype "input"))
    )
    (net (code "17") (name "GND") (class "Default")
      (node (ref "C1") (pin "1") (pinfunction "1_1") (pintype "passive"))
      (node (ref "C11") (pin "1") (pinfunction "1_1") (pintype "passive"))
      (node (ref "C12") (pin "1") (pinfunction "1_1") (pintype "passive"))
      (node (ref "C15") (pin "1") (pinfunction "1_1") (pintype "passive"))
      (node (ref "C17") (pin "2") (pinfunction "2_2") (pintype "passive"))
      (node (ref "C18") (pin "2") (pinfunction "2_2") (pintype "passive"))
      (node (ref "C19") (pin "1") (pinfunction "1_1") (pintype "passive"))
      (node (ref "C2") (pin "1") (pinfunction "1_1") (pintype "passive"))
      (node (ref "C22") (pin "1") (pinfunction "1_1") (pintype "passive"))
      (node (ref "C23") (pin "1") (pinfunction "1_1") (pintype "passive"))
      (node (ref "C24") (pin "1") (pinfunction "1_1") (pintype "passive"))
      (node (ref "C25") (pin "1") (pinfunction "1_1") (pintype "passive"))
      (node (ref "C26") (pin "1") (pinfunction "1_1") (pintype "passive"))
      (node (ref "C28") (pin "2") (pinfunction "2_2") (pintype "passive"))
      (node (ref "C29") (pin "1") (pinfunction "1_1") (pintype "passive"))
      (node (ref "C3") (pin "1") (pinfunction "1_1") (pintype "passive"))
      (node (ref "C30") (pin "1") (pinfunction "1_1") (pintype "passive"))
      (node (ref "C31") (pin "1") (pinfunction "1_1") (pintype "passive"))
      (node (ref "C32") (pin "2") (pinfunction "2_2") (pintype "passive"))
      (node (ref "C33") (pin "2") (pinfunction "2_2") (pintype "passive"))
      (node (ref "C34") (pin "2") (pinfunction "2_2") (pintype "passive"))
      (node (ref "C35") (pin "2") (pinfunction "2_2") (pintype "passive"))
      (node (ref "C36") (pin "2") (pinfunction "2_2") (pintype "passive"))
      (node (ref "C37") (pin "2") (pinfunction "2_2") (pintype "passive"))
      (node (ref "C38") (pin "2") (pinfunction "2_2") (pintype "passive"))
      (node (ref "C39") (pin "2") (pinfunction "2_2") (pintype "passive"))
      (node (ref "C4") (pin "1") (pinfunction "1_1") (pintype "passive"))
      (node (ref "C40") (pin "2") (pinfunction "2_2") (pintype "passive"))
      (node (ref "C41") (pin "2") (pinfunction "2_2") (pintype "passive"))
      (node (ref "C42") (pin "2") (pinfunction "2_2") (pintype "passive"))
      (node (ref "C43") (pin "2") (pinfunction "2_2") (pintype "passive"))
      (node (ref "C44") (pin "2") (pinfunction "2_2") (pintype "passive"))
      (node (ref "C45") (pin "2") (pinfunction "2_2") (pintype "passive"))
      (node (ref "C46") (pin "1") (pinfunction "1_1") (pintype "passive"))
      (node (ref "C47") (pin "2") (pinfunction "2_2") (pintype "passive"))
      (node (ref "C48") (pin "1") (pinfunction "1_1") (pintype "passive"))
      (node (ref "C49") (pin "2") (pinfunction "2_2") (pintype "passive"))
      (node (ref "C5") (pin "2") (pinfunction "2_2") (pintype "passive"))
      (node (ref "C50") (pin "2") (pinfunction "2_2") (pintype "passive"))
      (node (ref "C51") (pin "2") (pinfunction "2_2") (pintype "passive"))
      (node (ref "C6") (pin "1") (pinfunction "1_1") (pintype "passive"))
      (node (ref "C7") (pin "1") (pinfunction "1_1") (pintype "passive"))
      (node (ref "C8") (pin "1") (pinfunction "1_1") (pintype "passive"))
      (node (ref "C9") (pin "1") (pinfunction "1_1") (pintype "passive"))
      (node (ref "IC1") (pin "2") (pinfunction "GND_2") (pintype "passive"))
      (node (ref "J1") (pin "A1") (pinfunction "GND1_A1") (pintype "power_in"))
      (node (ref "J1") (pin "A12") (pinfunction "GND2_A12") (pintype "power_in"))
      (node (ref "J1") (pin "B1") (pinfunction "GND3_B1") (pintype "power_in"))
      (node (ref "J1") (pin "B12") (pinfunction "GND4_B12") (pintype "power_in"))
      (node (ref "J1") (pin "SH1") (pinfunction "SHIELD1_SH1") (pintype "passive"))
      (node (ref "J1") (pin "SH2") (pinfunction "SHIELD2_SH2") (pintype "passive"))
      (node (ref "J1") (pin "SH3") (pinfunction "SHIELD3_SH3") (pintype "passive"))
      (node (ref "J1") (pin "SH4") (pinfunction "SHIELD4_SH4") (pintype "passive"))
      (node (ref "J2") (pin "4") (pinfunction "4_4") (pintype "passive"))
      (node (ref "MK1") (pin "2") (pinfunction "GND_2") (pintype "power_in"))
      (node (ref "MK1") (pin "3") (pinfunction "GND_3") (pintype "power_in"))
      (node (ref "MK1") (pin "4") (pinfunction "GND_4") (pintype "power_in"))
      (node (ref "MK2") (pin "2") (pinfunction "GND_2") (pintype "power_in"))
      (node (ref "MK2") (pin "3") (pinfunction "GND_3") (pintype "power_in"))
      (node (ref "MK2") (pin "4") (pinfunction "GND_4") (pintype "power_in"))
      (node (ref "R1") (pin "2") (pinfunction "R2_2") (pintype "passive"))
      (node (ref "R11") (pin "2") (pinfunction "R2_2") (pintype "passive"))
      (node (ref "R12") (pin "2") (pinfunction "R2_2") (pintype "passive"))
      (node (ref "R14") (pin "1") (pinfunction "R1_1") (pintype "passive"))
      (node (ref "R15") (pin "1") (pinfunction "R1_1") (pintype "passive"))
      (node (ref "R16") (pin "2") (pinfunction "R2_2") (pintype "passive"))
      (node (ref "R2") (pin "1") (pinfunction "R1_1") (pintype "passive"))
      (node (ref "R24") (pin "2") (pinfunction "R2_2") (pintype "passive"))
      (node (ref "R26") (pin "2") (pinfunction "R2_2") (pintype "passive"))
      (node (ref "R4") (pin "2") (pinfunction "R2_2") (pintype "passive"))
      (node (ref "R6") (pin "1") (pinfunction "R1_1") (pintype "passive"))
      (node (ref "U1") (pin "1") (pinfunction "GND_1") (pintype "power_in"))
      (node (ref "U1") (pin "25") (pinfunction "GND_25") (pintype "power_in"))
      (node (ref "U1") (pin "37") (pinfunction "GND_37") (pintype "power_in"))
      (node (ref "U10") (pin "5") (pinfunction "REF_5") (pintype "input"))
      (node (ref "U2") (pin "6") (pinfunction "VSS_6") (pintype "power_in"))
      (node (ref "U5") (pin "3") (pinfunction "GND_3") (pintype "power_in"))
      (node (ref "U5") (pin "6") (pinfunction "LV_6") (pintype "bidirectional"))
      (node (ref "U6") (pin "5") (pinfunction "REF_5") (pintype "input"))
      (node (ref "U7") (pin "5") (pinfunction "REF_5") (pintype "input"))
      (node (ref "U9") (pin "2") (pinfunction "GND_2") (pintype "power_in"))
    )
    (net (code "18") (name "Net-(IC1-ADJ)") (class "Default")
      (node (ref "C34") (pin "1") (pinfunction "1_1") (pintype "passive"))
      (node (ref "IC1") (pin "4") (pinfunction "ADJ_4") (pintype "passive"))
      (node (ref "R13") (pin "2") (pinfunction "R2_2") (pintype "passive"))
      (node (ref "R16") (pin "1") (pinfunction "R1_1") (pintype "passive"))
    )
    (net (code "19") (name "Net-(J1-CC1)") (class "Default")
      (node (ref "J1") (pin "A5") (pinfunction "CC1_A5") (pintype "bidirectional"))
      (node (ref "R1") (pin "1") (pinfunction "R1_1") (pintype "passive"))
    )
    (net (code "20") (name "Net-(J1-CC2)") (class "Default")
      (node (ref "J1") (pin "B5") (pinfunction "CC2_B5") (pintype "bidirectional"))
      (node (ref "R2") (pin "2") (pinfunction "R2_2") (pintype "passive"))
    )
    (net (code "21") (name "Net-(MK1-OUT)") (class "Default")
      (node (ref "C20") (pin "2") (pinfunction "2_2") (pintype "passive"))
      (node (ref "MK1") (pin "1") (pinfunction "OUT_1") (pintype "output"))
    )
    (net (code "22") (name "Net-(MK2-OUT)") (class "Default")
      (node (ref "C21") (pin "2") (pinfunction "2_2") (pintype "passive"))
      (node (ref "MK2") (pin "1") (pinfunction "OUT_1") (pintype "output"))
    )
    (net (code "23") (name "Net-(R3-R1)") (class "Default")
      (node (ref "R3") (pin "1") (pinfunction "R1_1") (pintype "passive"))
      (node (ref "U2") (pin "5") (pinfunction "STAT_5") (pintype "output"))
    )
    (net (code "24") (name "Net-(R3-R2)") (class "Default")
      (node (ref "D1") (pin "C") (pinfunction "C_C") (pintype "passive"))
      (node (ref "R3") (pin "2") (pinfunction "R2_2") (pintype "passive"))
    )
    (net (code "25") (name "Net-(R4-R1)") (class "Default")
      (node (ref "C7") (pin "2") (pinfunction "2_2") (pintype "passive"))
      (node (ref "R4") (pin "1") (pinfunction "R1_1") (pintype "passive"))
      (node (ref "U2") (pin "8") (pinfunction "PROG_8") (pintype "input"))
    )
    (net (code "26") (name "Net-(R5-R2)") (class "Default")
      (node (ref "C13") (pin "1") (pinfunction "1_1") (pintype "passive"))
      (node (ref "C14") (pin "2") (pinfunction "2_2") (pintype "passive"))
      (node (ref "R5") (pin "2") (pinfunction "R2_2") (pintype "passive"))
    )
    (net (code "27") (name "Net-(R6-R2)") (class "Default")
      (node (ref "C14") (pin "1") (pinfunction "1_1") (pintype "passive"))
      (node (ref "R6") (pin "2") (pinfunction "R2_2") (pintype "passive"))
      (node (ref "U4") (pin "3") (pinfunction "+INA_3") (pintype "input"))
    )
    (net (code "28") (name "Net-(R7-R1)") (class "Default")
      (node (ref "C10") (pin "2") (pinfunction "2_2") (pintype "passive"))
      (node (ref "R7") (pin "1") (pinfunction "R1_1") (pintype "passive"))
      (node (ref "R8") (pin "2") (pinfunction "R2_2") (pintype "passive"))
    )
    (net (code "29") (name "Net-(R8-R1)") (class "Default")
      (node (ref "C11") (pin "2") (pinfunction "2_2") (pintype "passive"))
      (node (ref "R8") (pin "1") (pinfunction "R1_1") (pintype "passive"))
      (node (ref "U3") (pin "3") (pinfunction "+INA_3") (pintype "input"))
    )
    (net (code "30") (name "Net-(R10-R1)") (class "Default")
      (node (ref "C17") (pin "1") (pinfunction "1_1") (pintype "passive"))
      (node (ref "R10") (pin "1") (pinfunction "R1_1") (pintype "passive"))
      (node (ref "U4") (pin "5") (pinfunction "+INB_5") (pintype "input"))
    )
    (net (code "31") (name "Net-(R10-R2)") (class "Default")
      (node (ref "C16") (pin "1") (pinfunction "1_1") (pintype "passive"))
      (node (ref "R10") (pin "2") (pinfunction "R2_2") (pintype "passive"))
      (node (ref "R9") (pin "1") (pinfunction "R1_1") (pintype "passive"))
    )
    (net (code "32") (name "Net-(R17-R1)") (class "Default")
      (node (ref "R17") (pin "1") (pinfunction "R1_1") (pintype "passive"))
      (node (ref "U6") (pin "1") (pinfunction "RG1_1") (pintype "bidirectional"))
    )
    (net (code "33") (name "Net-(R17-R2)") (class "Default")
      (node (ref "R17") (pin "2") (pinfunction "R2_2") (pintype "passive"))
      (node (ref "U6") (pin "8") (pinfunction "RG2_8") (pintype "bidirectional"))
    )
    (net (code "34") (name "Net-(R18-R1)") (class "Default")
      (node (ref "R18") (pin "1") (pinfunction "R1_1") (pintype "passive"))
      (node (ref "U7") (pin "1") (pinfunction "RG1_1") (pintype "bidirectional"))
    )
    (net (code "35") (name "Net-(R18-R2)") (class "Default")
      (node (ref "R18") (pin "2") (pinfunction "R2_2") (pintype "passive"))
      (node (ref "U7") (pin "8") (pinfunction "RG2_8") (pintype "bidirectional"))
    )
    (net (code "36") (name "Net-(R19-R2)") (class "Default")
      (node (ref "R19") (pin "2") (pinfunction "R2_2") (pintype "passive"))
      (node (ref "R20") (pin "1") (pinfunction "R1_1") (pintype "passive"))
      (node (ref "U8") (pin "3") (pinfunction "+INA_3") (pintype "input"))
    )
    (net (code "37") (name "Net-(R21-R1)") (class "Default")
      (node (ref "R21") (pin "1") (pinfunction "R1_1") (pintype "passive"))
      (node (ref "U10") (pin "3") (pinfunction "+IN_3") (pintype "input"))
    )
    (net (code "38") (name "Net-(R22-R2)") (class "Default")
      (node (ref "R22") (pin "2") (pinfunction "R2_2") (pintype "passive"))
      (node (ref "R26") (pin "1") (pinfunction "R1_1") (pintype "passive"))
      (node (ref "U9") (pin "1") (pinfunction "ADJ_1") (pintype "bidirectional"))
    )
    (net (code "39") (name "Net-(R23-R2)") (class "Default")
      (node (ref "R23") (pin "2") (pinfunction "R2_2") (pintype "passive"))
      (node (ref "U10") (pin "2") (pinfunction "-IN_2") (pintype "input"))
    )
    (net (code "40") (name "Net-(R24-R1)") (class "Default")
      (node (ref "R24") (pin "1") (pinfunction "R1_1") (pintype "passive"))
      (node (ref "R25") (pin "2") (pinfunction "R2_2") (pintype "passive"))
      (node (ref "U8") (pin "2") (pinfunction "-INA_2") (pintype "input"))
    )
    (net (code "41") (name "Net-(U5-CAP+)") (class "Default")
      (node (ref "C27") (pin "2") (pinfunction "2_2") (pintype "passive"))
      (node (ref "U5") (pin "2") (pinfunction "CAP+_2") (pintype "bidirectional"))
    )
    (net (code "42") (name "Net-(U5-CAP-)") (class "Default")
      (node (ref "C27") (pin "1") (pinfunction "1_1") (pintype "passive"))
      (node (ref "U5") (pin "4") (pinfunction "CAP-_4") (pintype "bidirectional"))
    )
    (net (code "43") (name "Ref") (class "Default")
      (node (ref "C43") (pin "1") (pinfunction "1_1") (pintype "passive"))
      (node (ref "R19") (pin "1") (pinfunction "R1_1") (pintype "passive"))
      (node (ref "R22") (pin "1") (pinfunction "R1_1") (pintype "passive"))
      (node (ref "U9") (pin "5") (pinfunction "OUT_5") (pintype "output"))
    )
    (net (code "44") (name "VDD_-3.3V") (class "Default")
      (node (ref "C18") (pin "1") (pinfunction "1_1") (pintype "passive"))
      (node (ref "C19") (pin "2") (pinfunction "2_2") (pintype "passive"))
      (node (ref "C29") (pin "2") (pinfunction "2_2") (pintype "passive"))
      (node (ref "C30") (pin "2") (pinfunction "2_2") (pintype "passive"))
      (node (ref "C31") (pin "2") (pinfunction "2_2") (pintype "passive"))
      (node (ref "C39") (pin "1") (pinfunction "1_1") (pintype "passive"))
      (node (ref "C40") (pin "1") (pinfunction "1_1") (pintype "passive"))
      (node (ref "C41") (pin "1") (pinfunction "1_1") (pintype "passive"))
      (node (ref "C42") (pin "1") (pinfunction "1_1") (pintype "passive"))
      (node (ref "C48") (pin "2") (pinfunction "2_2") (pintype "passive"))
      (node (ref "C50") (pin "1") (pinfunction "1_1") (pintype "passive"))
      (node (ref "C51") (pin "1") (pinfunction "1_1") (pintype "passive"))
      (node (ref "U10") (pin "4") (pinfunction "-VS_4") (pintype "bidirectional"))
      (node (ref "U3") (pin "4") (pinfunction "V-_4") (pintype "power_in"))
      (node (ref "U4") (pin "4") (pinfunction "V-_4") (pintype "power_in"))
      (node (ref "U5") (pin "5") (pinfunction "VOUT_5") (pintype "output"))
      (node (ref "U6") (pin "4") (pinfunction "-VS_4") (pintype "bidirectional"))
      (node (ref "U7") (pin "4") (pinfunction "-VS_4") (pintype "bidirectional"))
      (node (ref "U8") (pin "4") (pinfunction "V-_4") (pintype "power_in"))
    )
    (net (code "45") (name "VDD_3.3V") (class "Default")
      (node (ref "C12") (pin "2") (pinfunction "2_2") (pintype "passive"))
      (node (ref "C15") (pin "2") (pinfunction "2_2") (pintype "passive"))
      (node (ref "C22") (pin "2") (pinfunction "2_2") (pintype "passive"))
      (node (ref "C23") (pin "2") (pinfunction "2_2") (pintype "passive"))
      (node (ref "C24") (pin "2") (pinfunction "2_2") (pintype "passive"))
      (node (ref "C25") (pin "2") (pinfunction "2_2") (pintype "passive"))
      (node (ref "C26") (pin "2") (pinfunction "2_2") (pintype "passive"))
      (node (ref "C28") (pin "1") (pinfunction "1_1") (pintype "passive"))
      (node (ref "C3") (pin "2") (pinfunction "2_2") (pintype "passive"))
      (node (ref "C35") (pin "1") (pinfunction "1_1") (pintype "passive"))
      (node (ref "C36") (pin "1") (pinfunction "1_1") (pintype "passive"))
      (node (ref "C37") (pin "1") (pinfunction "1_1") (pintype "passive"))
      (node (ref "C38") (pin "1") (pinfunction "1_1") (pintype "passive"))
      (node (ref "C4") (pin "2") (pinfunction "2_2") (pintype "passive"))
      (node (ref "C44") (pin "1") (pinfunction "1_1") (pintype "passive"))
      (node (ref "C45") (pin "1") (pinfunction "1_1") (pintype "passive"))
      (node (ref "C46") (pin "2") (pinfunction "2_2") (pintype "passive"))
      (node (ref "C47") (pin "1") (pinfunction "1_1") (pintype "passive"))
      (node (ref "C49") (pin "1") (pinfunction "1_1") (pintype "passive"))
      (node (ref "IC1") (pin "5") (pinfunction "OUT_5") (pintype "passive"))
      (node (ref "J2") (pin "1") (pinfunction "1_1") (pintype "passive"))
      (node (ref "MK1") (pin "5") (pinfunction "VDD_5") (pintype "power_in"))
      (node (ref "MK2") (pin "5") (pinfunction "VDD_5") (pintype "power_in"))
      (node (ref "R13") (pin "1") (pinfunction "R1_1") (pintype "passive"))
      (node (ref "U1") (pin "14") (pinfunction "VDD_NRF_14") (pintype "power_in"))
      (node (ref "U10") (pin "7") (pinfunction "+VS_7") (pintype "bidirectional"))
      (node (ref "U3") (pin "8") (pinfunction "V+_8") (pintype "power_in"))
      (node (ref "U4") (pin "8") (pinfunction "V+_8") (pintype "power_in"))
      (node (ref "U5") (pin "8") (pinfunction "V+_8") (pintype "power_in"))
      (node (ref "U6") (pin "7") (pinfunction "+VS_7") (pintype "bidirectional"))
      (node (ref "U7") (pin "7") (pinfunction "+VS_7") (pintype "bidirectional"))
      (node (ref "U8") (pin "8") (pinfunction "V+_8") (pintype "power_in"))
      (node (ref "U9") (pin "3") (pinfunction "EN_3") (pintype "bidirectional"))
      (node (ref "U9") (pin "4") (pinfunction "IN_4") (pintype "input"))
    )
    (net (code "46") (name "V_BATT") (class "Default")
      (node (ref "C32") (pin "1") (pinfunction "1_1") (pintype "passive"))
      (node (ref "C33") (pin "1") (pinfunction "1_1") (pintype "passive"))
      (node (ref "C5") (pin "1") (pinfunction "1_1") (pintype "passive"))
      (node (ref "IC1") (pin "1") (pinfunction "IN_1") (pintype "passive"))
      (node (ref "IC1") (pin "3") (pinfunction "EN_3") (pintype "passive"))
      (node (ref "U2") (pin "3") (pinfunction "VBAT_3") (pintype "output"))
    )
    (net (code "47") (name "V_USB") (class "Default")
      (node (ref "C1") (pin "2") (pinfunction "2_2") (pintype "passive"))
      (node (ref "C2") (pin "2") (pinfunction "2_2") (pintype "passive"))
      (node (ref "C6") (pin "2") (pinfunction "2_2") (pintype "passive"))
      (node (ref "C8") (pin "2") (pinfunction "2_2") (pintype "passive"))
      (node (ref "C9") (pin "2") (pinfunction "2_2") (pintype "passive"))
      (node (ref "D1") (pin "A") (pinfunction "A_A") (pintype "passive"))
      (node (ref "J1") (pin "A4") (pinfunction "VBUS1_A4") (pintype "power_in"))
      (node (ref "J1") (pin "A9") (pinfunction "VBUS2_A9") (pintype "power_in"))
      (node (ref "J1") (pin "B4") (pinfunction "VBUS3_B4") (pintype "power_in"))
      (node (ref "J1") (pin "B9") (pinfunction "VBUS4_B9") (pintype "power_in"))
      (node (ref "U1") (pin "22") (pinfunction "VBUS_22") (pintype "power_in"))
      (node (ref "U2") (pin "1") (pinfunction "VDD_1") (pintype "power_in"))
      (node (ref "U2") (pin "2") (pinfunction "VDD_2") (pintype "power_in"))
    )
    (net (code "48") (name "unconnected-(J1-DA+-PadA6)") (class "Default")
      (node (ref "J1") (pin "A6") (pinfunction "DA+_A6") (pintype "bidirectional"))
    )
    (net (code "49") (name "unconnected-(J1-DA--PadA7)") (class "Default")
      (node (ref "J1") (pin "A7") (pinfunction "DA-_A7") (pintype "bidirectional"))
    )
    (net (code "50") (name "unconnected-(J1-DB+-PadB6)") (class "Default")
      (node (ref "J1") (pin "B6") (pinfunction "DB+_B6") (pintype "bidirectional"))
    )
    (net (code "51") (name "unconnected-(J1-DB--PadB7)") (class "Default")
      (node (ref "J1") (pin "B7") (pinfunction "DB-_B7") (pintype "bidirectional"))
    )
    (net (code "52") (name "unconnected-(J1-SBU1-PadA8)") (class "Default")
      (node (ref "J1") (pin "A8") (pinfunction "SBU1_A8") (pintype "bidirectional"))
    )
    (net (code "53") (name "unconnected-(J1-SBU2-PadB8)") (class "Default")
      (node (ref "J1") (pin "B8") (pinfunction "SBU2_B8") (pintype "bidirectional"))
    )
    (net (code "54") (name "unconnected-(U1-DN-Pad23)") (class "Default")
      (node (ref "U1") (pin "23") (pinfunction "DN_23") (pintype "bidirectional"))
    )
    (net (code "55") (name "unconnected-(U1-DP-Pad24)") (class "Default")
      (node (ref "U1") (pin "24") (pinfunction "DP_24") (pintype "bidirectional"))
    )
    (net (code "56") (name "unconnected-(U1-P0_03-Pad6)") (class "Default")
      (node (ref "U1") (pin "6") (pinfunction "P0_03_6") (pintype "bidirectional"))
    )
    (net (code "57") (name "unconnected-(U1-P0_04-Pad12)") (class "Default")
      (node (ref "U1") (pin "12") (pinfunction "P0_04_12") (pintype "bidirectional"))
    )
    (net (code "58") (name "unconnected-(U1-P0_05-Pad13)") (class "Default")
      (node (ref "U1") (pin "13") (pinfunction "P0_05_13") (pintype "bidirectional"))
    )
    (net (code "59") (name "unconnected-(U1-P0_06-Pad45)") (class "Default")
      (node (ref "U1") (pin "45") (pinfunction "P0_06_45") (pintype "bidirectional"))
    )
    (net (code "60") (name "unconnected-(U1-P0_07-Pad15)") (class "Default")
      (node (ref "U1") (pin "15") (pinfunction "P0_07_15") (pintype "bidirectional"))
    )
    (net (code "61") (name "unconnected-(U1-P0_08-Pad44)") (class "Default")
      (node (ref "U1") (pin "44") (pinfunction "P0_08_44") (pintype "bidirectional"))
    )
    (net (code "62") (name "unconnected-(U1-P0_09-Pad35)") (class "Default")
      (node (ref "U1") (pin "35") (pinfunction "P0_09_35") (pintype "bidirectional"))
    )
    (net (code "63") (name "unconnected-(U1-P0_10-Pad36)") (class "Default")
      (node (ref "U1") (pin "36") (pinfunction "P0_10_36") (pintype "bidirectional"))
    )
    (net (code "64") (name "unconnected-(U1-P0_11-Pad41)") (class "Default")
      (node (ref "U1") (pin "41") (pinfunction "P0_11_41") (pintype "bidirectional"))
    )
    (net (code "65") (name "unconnected-(U1-P0_12-Pad17)") (class "Default")
      (node (ref "U1") (pin "17") (pinfunction "P0_12_17") (pintype "bidirectional"))
    )
    (net (code "66") (name "unconnected-(U1-P0_13-Pad54)") (class "Default")
      (node (ref "U1") (pin "54") (pinfunction "P0_13_54") (pintype "bidirectional"))
    )
    (net (code "67") (name "unconnected-(U1-P0_14-Pad53)") (class "Default")
      (node (ref "U1") (pin "53") (pinfunction "P0_14_53") (pintype "bidirectional"))
    )
    (net (code "68") (name "unconnected-(U1-P0_15-Pad52)") (class "Default")
      (node (ref "U1") (pin "52") (pinfunction "P0_15_52") (pintype "bidirectional"))
    )
    (net (code "69") (name "unconnected-(U1-P0_16-Pad55)") (class "Default")
      (node (ref "U1") (pin "55") (pinfunction "P0_16_55") (pintype "bidirectional"))
    )
    (net (code "70") (name "unconnected-(U1-P0_17-Pad51)") (class "Default")
      (node (ref "U1") (pin "51") (pinfunction "P0_17_51") (pintype "bidirectional"))
    )
    (net (code "71") (name "unconnected-(U1-P0_18-Pad21)") (class "Default")
      (node (ref "U1") (pin "21") (pinfunction "P0_18_21") (pintype "bidirectional"))
    )
    (net (code "72") (name "unconnected-(U1-P0_19-Pad20)") (class "Default")
      (node (ref "U1") (pin "20") (pinfunction "P0_19_20") (pintype "bidirectional"))
    )
    (net (code "73") (name "unconnected-(U1-P0_20-Pad50)") (class "Default")
      (node (ref "U1") (pin "50") (pinfunction "P0_20_50") (pintype "bidirectional"))
    )
    (net (code "74") (name "unconnected-(U1-P0_21-Pad19)") (class "Default")
      (node (ref "U1") (pin "19") (pinfunction "P0_21_19") (pintype "bidirectional"))
    )
    (net (code "75") (name "unconnected-(U1-P0_22-Pad26)") (class "Default")
      (node (ref "U1") (pin "26") (pinfunction "P0_22_26") (pintype "bidirectional"))
    )
    (net (code "76") (name "unconnected-(U1-P0_23-Pad18)") (class "Default")
      (node (ref "U1") (pin "18") (pinfunction "P0_23_18") (pintype "bidirectional"))
    )
    (net (code "77") (name "unconnected-(U1-P0_24-Pad49)") (class "Default")
      (node (ref "U1") (pin "49") (pinfunction "P0_24_49") (pintype "bidirectional"))
    )
    (net (code "78") (name "unconnected-(U1-P0_25-Pad40)") (class "Default")
      (node (ref "U1") (pin "40") (pinfunction "P0_25_40") (pintype "bidirectional"))
    )
    (net (code "79") (name "unconnected-(U1-P0_26-Pad46)") (class "Default")
      (node (ref "U1") (pin "46") (pinfunction "P0_26_46") (pintype "bidirectional"))
    )
    (net (code "80") (name "unconnected-(U1-P0_27-Pad43)") (class "Default")
      (node (ref "U1") (pin "43") (pinfunction "P0_27_43") (pintype "bidirectional"))
    )
    (net (code "81") (name "unconnected-(U1-P0_28-Pad8)") (class "Default")
      (node (ref "U1") (pin "8") (pinfunction "P0_28_8") (pintype "bidirectional"))
    )
    (net (code "82") (name "unconnected-(U1-P0_29-Pad9)") (class "Default")
      (node (ref "U1") (pin "9") (pinfunction "P0_29_9") (pintype "bidirectional"))
    )
    (net (code "83") (name "unconnected-(U1-P0_30-Pad10)") (class "Default")
      (node (ref "U1") (pin "10") (pinfunction "P0_30_10") (pintype "bidirectional"))
    )
    (net (code "84") (name "unconnected-(U1-P0_31-Pad11)") (class "Default")
      (node (ref "U1") (pin "11") (pinfunction "P0_31_11") (pintype "bidirectional"))
    )
    (net (code "85") (name "unconnected-(U1-P1_00-Pad27)") (class "Default")
      (node (ref "U1") (pin "27") (pinfunction "P1_00_27") (pintype "bidirectional"))
    )
    (net (code "86") (name "unconnected-(U1-P1_01-Pad29)") (class "Default")
      (node (ref "U1") (pin "29") (pinfunction "P1_01_29") (pintype "bidirectional"))
    )
    (net (code "87") (name "unconnected-(U1-P1_02-Pad30)") (class "Default")
      (node (ref "U1") (pin "30") (pinfunction "P1_02_30") (pintype "bidirectional"))
    )
    (net (code "88") (name "unconnected-(U1-P1_03-Pad28)") (class "Default")
      (node (ref "U1") (pin "28") (pinfunction "P1_03_28") (pintype "bidirectional"))
    )
    (net (code "89") (name "unconnected-(U1-P1_04-Pad33)") (class "Default")
      (node (ref "U1") (pin "33") (pinfunction "P1_04_33") (pintype "bidirectional"))
    )
    (net (code "90") (name "unconnected-(U1-P1_05-Pad48)") (class "Default")
      (node (ref "U1") (pin "48") (pinfunction "P1_05_48") (pintype "bidirectional"))
    )
    (net (code "91") (name "unconnected-(U1-P1_06-Pad34)") (class "Default")
      (node (ref "U1") (pin "34") (pinfunction "P1_06_34") (pintype "bidirectional"))
    )
    (net (code "92") (name "unconnected-(U1-P1_07-Pad47)") (class "Default")
      (node (ref "U1") (pin "47") (pinfunction "P1_07_47") (pintype "bidirectional"))
    )
    (net (code "93") (name "unconnected-(U1-P1_08-Pad42)") (class "Default")
      (node (ref "U1") (pin "42") (pinfunction "P1_08_42") (pintype "bidirectional"))
    )
    (net (code "94") (name "unconnected-(U1-P1_09-Pad16)") (class "Default")
      (node (ref "U1") (pin "16") (pinfunction "P1_09_16") (pintype "bidirectional"))
    )
    (net (code "95") (name "unconnected-(U1-P1_10-Pad3)") (class "Default")
      (node (ref "U1") (pin "3") (pinfunction "P1_10_3") (pintype "bidirectional"))
    )
    (net (code "96") (name "unconnected-(U1-P1_11-Pad2)") (class "Default")
      (node (ref "U1") (pin "2") (pinfunction "P1_11_2") (pintype "bidirectional"))
    )
    (net (code "97") (name "unconnected-(U1-P1_12-Pad39)") (class "Default")
      (node (ref "U1") (pin "39") (pinfunction "P1_12_39") (pintype "bidirectional"))
    )
    (net (code "98") (name "unconnected-(U1-P1_13-Pad4)") (class "Default")
      (node (ref "U1") (pin "4") (pinfunction "P1_13_4") (pintype "bidirectional"))
    )
    (net (code "99") (name "unconnected-(U1-P1_14-Pad38)") (class "Default")
      (node (ref "U1") (pin "38") (pinfunction "P1_14_38") (pintype "bidirectional"))
    )
    (net (code "100") (name "unconnected-(U1-P1_15-Pad5)") (class "Default")
      (node (ref "U1") (pin "5") (pinfunction "P1_15_5") (pintype "bidirectional"))
    )
    (net (code "101") (name "unconnected-(U2-EP-Pad9)") (class "Default")
      (node (ref "U2") (pin "9") (pinfunction "EP_9") (pintype "power_in"))
    )
    (net (code "102") (name "unconnected-(U2-VBAT-Pad4)") (class "Default")
      (node (ref "U2") (pin "4") (pinfunction "VBAT_4") (pintype "output"))
    )
    (net (code "103") (name "unconnected-(U3-+INB-Pad5)") (class "Default")
      (node (ref "U3") (pin "5") (pinfunction "+INB_5") (pintype "input+no_connect"))
    )
    (net (code "104") (name "unconnected-(U3--INB-Pad6)") (class "Default")
      (node (ref "U3") (pin "6") (pinfunction "-INB_6") (pintype "input+no_connect"))
    )
    (net (code "105") (name "unconnected-(U3-OUTB-Pad7)") (class "Default")
      (node (ref "U3") (pin "7") (pinfunction "OUTB_7") (pintype "output"))
    )
    (net (code "106") (name "unconnected-(U5-(NC)BOOST-Pad1)") (class "Default")
      (node (ref "U5") (pin "1") (pinfunction "(NC)BOOST_1") (pintype "bidirectional"))
    )
    (net (code "107") (name "unconnected-(U5-OSC-Pad7)") (class "Default")
      (node (ref "U5") (pin "7") (pinfunction "OSC_7") (pintype "bidirectional"))
    )
    (net (code "108") (name "unconnected-(U8-+INB-Pad5)") (class "Default")
      (node (ref "U8") (pin "5") (pinfunction "+INB_5") (pintype "input+no_connect"))
    )
    (net (code "109") (name "unconnected-(U8--INB-Pad6)") (class "Default")
      (node (ref "U8") (pin "6") (pinfunction "-INB_6") (pintype "input+no_connect"))
    )
    (net (code "110") (name "unconnected-(U8-OUTB-Pad7)") (class "Default")
      (node (ref "U8") (pin "7") (pinfunction "OUTB_7") (pintype "output"))
    )
    (net (code "111") (name "unconnected-(U10-RG1-Pad1)") (class "Default")
      (node (ref "U10") (pin "1") (pinfunction "RG1_1") (pintype "bidirectional"))
    )
    (net (code "112") (name "unconnected-(U10-RG2-Pad8)") (class "Default")
      (node (ref "U10") (pin "8") (pinfunction "RG2_8") (pintype "bidirectional"))
    )
  )
)
